# m907-vu-meter.net
KiCad netlist of a schematic drawn in EAGLE
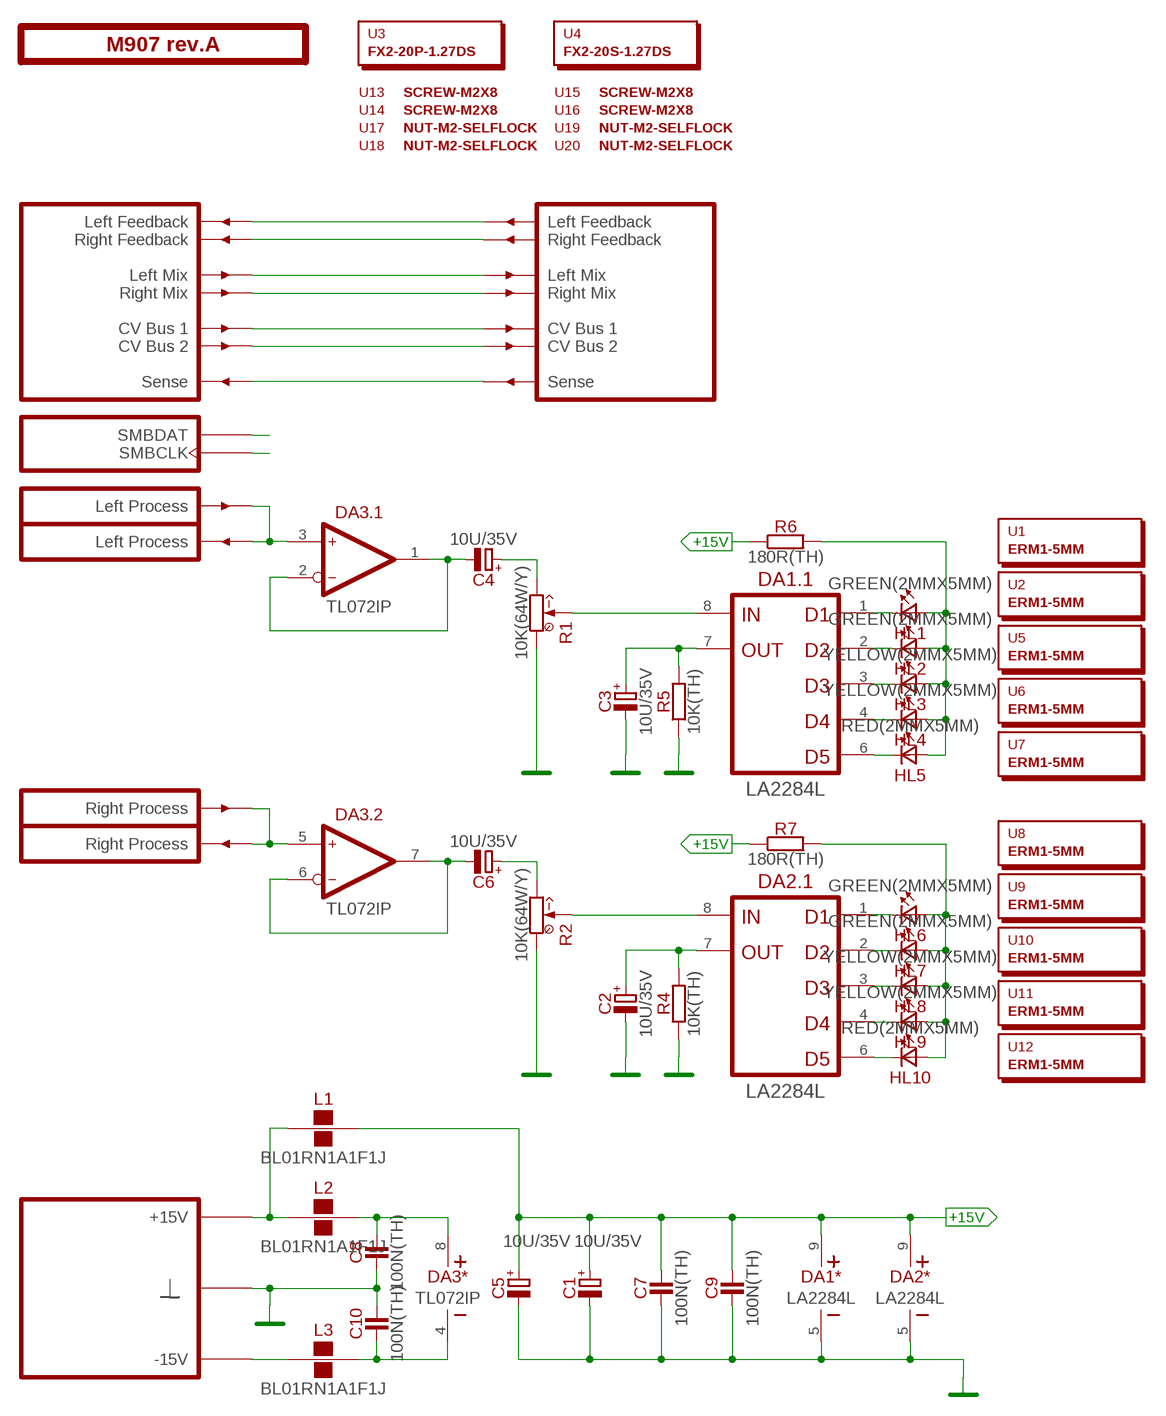
[diagram p0: schematic, sheet 1]

(export (version "E")
  (design (tool "Eeschema 10.0.6"))
  (components
    (comp (ref "C1")
      (value "10U/35V")
      (footprint "eagle-import:E2-5")
      (libsource (lib "eagle-import") (part "?10U/35V"))
    )
    (comp (ref "C2")
      (value "10U/35V")
      (footprint "eagle-import:E2-5")
      (libsource (lib "eagle-import") (part "?10U/35V"))
    )
    (comp (ref "C3")
      (value "10U/35V")
      (footprint "eagle-import:E2-5")
      (libsource (lib "eagle-import") (part "?10U/35V"))
    )
    (comp (ref "C4")
      (value "10U/35V")
      (footprint "eagle-import:E2-5")
      (libsource (lib "eagle-import") (part "?10U/35V"))
    )
    (comp (ref "C5")
      (value "10U/35V")
      (footprint "eagle-import:E2-5")
      (libsource (lib "eagle-import") (part "?10U/35V"))
    )
    (comp (ref "C6")
      (value "10U/35V")
      (footprint "eagle-import:E2-5")
      (libsource (lib "eagle-import") (part "?10U/35V"))
    )
    (comp (ref "C7")
      (value "100N(TH)")
      (footprint "eagle-import:C050-024X044")
      (libsource (lib "eagle-import") (part "?100N(TH)"))
    )
    (comp (ref "C8")
      (value "100N(TH)")
      (footprint "eagle-import:C050-024X044")
      (libsource (lib "eagle-import") (part "?100N(TH)"))
    )
    (comp (ref "C9")
      (value "100N(TH)")
      (footprint "eagle-import:C050-024X044")
      (libsource (lib "eagle-import") (part "?100N(TH)"))
    )
    (comp (ref "C10")
      (value "100N(TH)")
      (footprint "eagle-import:C050-024X044")
      (libsource (lib "eagle-import") (part "?100N(TH)"))
    )
    (comp (ref "DA1")
      (value "LA2284L")
      (footprint "eagle-import:SIL9")
      (libsource (lib "eagle-import") (part "LA2284L"))
    )
    (comp (ref "DA2")
      (value "LA2284L")
      (footprint "eagle-import:SIL9")
      (libsource (lib "eagle-import") (part "LA2284L"))
    )
    (comp (ref "DA3")
      (value "TL072IP")
      (footprint "eagle-import:DIP-8")
      (libsource (lib "eagle-import") (part "TL072IP"))
    )
    (comp (ref "HL1")
      (value "GREEN(2MMX5MM)")
      (footprint "eagle-import:LED2X5")
      (libsource (lib "eagle-import") (part "?(2MMX5MM)GREEN"))
    )
    (comp (ref "HL2")
      (value "GREEN(2MMX5MM)")
      (footprint "eagle-import:LED2X5")
      (libsource (lib "eagle-import") (part "?(2MMX5MM)GREEN"))
    )
    (comp (ref "HL3")
      (value "YELLOW(2MMX5MM)")
      (footprint "eagle-import:LED2X5")
      (libsource (lib "eagle-import") (part "?(2MMX5MM)YELLOW"))
    )
    (comp (ref "HL4")
      (value "YELLOW(2MMX5MM)")
      (footprint "eagle-import:LED2X5")
      (libsource (lib "eagle-import") (part "?(2MMX5MM)YELLOW"))
    )
    (comp (ref "HL5")
      (value "RED(2MMX5MM)")
      (footprint "eagle-import:LED2X5")
      (libsource (lib "eagle-import") (part "?(2MMX5MM)RED"))
    )
    (comp (ref "HL6")
      (value "GREEN(2MMX5MM)")
      (footprint "eagle-import:LED2X5")
      (libsource (lib "eagle-import") (part "?(2MMX5MM)GREEN"))
    )
    (comp (ref "HL7")
      (value "GREEN(2MMX5MM)")
      (footprint "eagle-import:LED2X5")
      (libsource (lib "eagle-import") (part "?(2MMX5MM)GREEN"))
    )
    (comp (ref "HL8")
      (value "YELLOW(2MMX5MM)")
      (footprint "eagle-import:LED2X5")
      (libsource (lib "eagle-import") (part "?(2MMX5MM)YELLOW"))
    )
    (comp (ref "HL9")
      (value "YELLOW(2MMX5MM)")
      (footprint "eagle-import:LED2X5")
      (libsource (lib "eagle-import") (part "?(2MMX5MM)YELLOW"))
    )
    (comp (ref "HL10")
      (value "RED(2MMX5MM)")
      (footprint "eagle-import:LED2X5")
      (libsource (lib "eagle-import") (part "?(2MMX5MM)RED"))
    )
    (comp (ref "L1")
      (value "BL01RN1A1F1J")
      (footprint "eagle-import:BL01RN1A")
      (libsource (lib "eagle-import") (part "BL01RN1A?1F1J"))
    )
    (comp (ref "L2")
      (value "BL01RN1A1F1J")
      (footprint "eagle-import:BL01RN1A")
      (libsource (lib "eagle-import") (part "BL01RN1A?1F1J"))
    )
    (comp (ref "L3")
      (value "BL01RN1A1F1J")
      (footprint "eagle-import:BL01RN1A")
      (libsource (lib "eagle-import") (part "BL01RN1A?1F1J"))
    )
    (comp (ref "PCB1")
      (value "M907 rev.A")
      (footprint "eagle-import:ST2-BOARD-26")
      (libsource (lib "eagle-import") (part "ST2-BOARD-?26"))
    )
    (comp (ref "R1")
      (value "10K(64W/Y)")
      (footprint "eagle-import:64W")
      (libsource (lib "eagle-import") (part "?(64W/Y)10K"))
    )
    (comp (ref "R2")
      (value "10K(64W/Y)")
      (footprint "eagle-import:64W")
      (libsource (lib "eagle-import") (part "?(64W/Y)10K"))
    )
    (comp (ref "R4")
      (value "10K(TH)")
      (footprint "eagle-import:R-0207_10")
      (libsource (lib "eagle-import") (part "?10K(TH)"))
    )
    (comp (ref "R5")
      (value "10K(TH)")
      (footprint "eagle-import:R-0207_10")
      (libsource (lib "eagle-import") (part "?10K(TH)"))
    )
    (comp (ref "R6")
      (value "180R(TH)")
      (footprint "eagle-import:R-0207_10")
      (libsource (lib "eagle-import") (part "?180R(TH)"))
    )
    (comp (ref "R7")
      (value "180R(TH)")
      (footprint "eagle-import:R-0207_10")
      (libsource (lib "eagle-import") (part "?180R(TH)"))
    )
    (comp (ref "U1")
      (value "ERM1-5MM")
      (footprint "eagle-import:EMPTY")
      (libsource (lib "eagle-import") (part "?ERM1-5MM"))
    )
    (comp (ref "U2")
      (value "ERM1-5MM")
      (footprint "eagle-import:EMPTY")
      (libsource (lib "eagle-import") (part "?ERM1-5MM"))
    )
    (comp (ref "U3")
      (value "FX2-20P-1.27DS")
      (footprint "eagle-import:EMPTY")
      (libsource (lib "eagle-import") (part "?FX2-20P-1.27DS"))
    )
    (comp (ref "U4")
      (value "FX2-20S-1.27DS")
      (footprint "eagle-import:EMPTY")
      (libsource (lib "eagle-import") (part "?FX2-20S-1.27DS"))
    )
    (comp (ref "U5")
      (value "ERM1-5MM")
      (footprint "eagle-import:EMPTY")
      (libsource (lib "eagle-import") (part "?ERM1-5MM"))
    )
    (comp (ref "U6")
      (value "ERM1-5MM")
      (footprint "eagle-import:EMPTY")
      (libsource (lib "eagle-import") (part "?ERM1-5MM"))
    )
    (comp (ref "U7")
      (value "ERM1-5MM")
      (footprint "eagle-import:EMPTY")
      (libsource (lib "eagle-import") (part "?ERM1-5MM"))
    )
    (comp (ref "U8")
      (value "ERM1-5MM")
      (footprint "eagle-import:EMPTY")
      (libsource (lib "eagle-import") (part "?ERM1-5MM"))
    )
    (comp (ref "U9")
      (value "ERM1-5MM")
      (footprint "eagle-import:EMPTY")
      (libsource (lib "eagle-import") (part "?ERM1-5MM"))
    )
    (comp (ref "U10")
      (value "ERM1-5MM")
      (footprint "eagle-import:EMPTY")
      (libsource (lib "eagle-import") (part "?ERM1-5MM"))
    )
    (comp (ref "U11")
      (value "ERM1-5MM")
      (footprint "eagle-import:EMPTY")
      (libsource (lib "eagle-import") (part "?ERM1-5MM"))
    )
    (comp (ref "U12")
      (value "ERM1-5MM")
      (footprint "eagle-import:EMPTY")
      (libsource (lib "eagle-import") (part "?ERM1-5MM"))
    )
    (comp (ref "U13")
      (value "SCREW-M2X8")
      (footprint "eagle-import:EMPTY")
      (libsource (lib "eagle-import") (part "?SCREW-M2X8"))
    )
    (comp (ref "U14")
      (value "SCREW-M2X8")
      (footprint "eagle-import:EMPTY")
      (libsource (lib "eagle-import") (part "?SCREW-M2X8"))
    )
    (comp (ref "U15")
      (value "SCREW-M2X8")
      (footprint "eagle-import:EMPTY")
      (libsource (lib "eagle-import") (part "?SCREW-M2X8"))
    )
    (comp (ref "U16")
      (value "SCREW-M2X8")
      (footprint "eagle-import:EMPTY")
      (libsource (lib "eagle-import") (part "?SCREW-M2X8"))
    )
    (comp (ref "U17")
      (value "NUT-M2-SELFLOCK")
      (footprint "eagle-import:EMPTY")
      (libsource (lib "eagle-import") (part "?NUT-M2-SELFLOCK"))
    )
    (comp (ref "U18")
      (value "NUT-M2-SELFLOCK")
      (footprint "eagle-import:EMPTY")
      (libsource (lib "eagle-import") (part "?NUT-M2-SELFLOCK"))
    )
    (comp (ref "U19")
      (value "NUT-M2-SELFLOCK")
      (footprint "eagle-import:EMPTY")
      (libsource (lib "eagle-import") (part "?NUT-M2-SELFLOCK"))
    )
    (comp (ref "U20")
      (value "NUT-M2-SELFLOCK")
      (footprint "eagle-import:EMPTY")
      (libsource (lib "eagle-import") (part "?NUT-M2-SELFLOCK"))
    )
  )
  (nets
    (net (code "1") (name "+15V") (class "Default")
      (node (ref "C1") (pin "+") (pinfunction "+_+") (pintype "passive"))
      (node (ref "C5") (pin "+") (pinfunction "+_+") (pintype "passive"))
      (node (ref "C7") (pin "2") (pinfunction "2_2") (pintype "passive"))
      (node (ref "C9") (pin "2") (pinfunction "2_2") (pintype "passive"))
      (node (ref "DA1") (pin "9") (pinfunction "V+_9") (pintype "power_in"))
      (node (ref "DA2") (pin "9") (pinfunction "V+_9") (pintype "power_in"))
      (node (ref "L1") (pin "2") (pinfunction "2_2") (pintype "passive"))
      (node (ref "R6") (pin "1") (pinfunction "1_1") (pintype "passive"))
      (node (ref "R7") (pin "1") (pinfunction "1_1") (pintype "passive"))
    )
    (net (code "2") (name "GND") (class "Default")
      (node (ref "C1") (pin "-") (pinfunction "-_-") (pintype "passive"))
      (node (ref "C10") (pin "2") (pinfunction "2_2") (pintype "passive"))
      (node (ref "C2") (pin "-") (pinfunction "-_-") (pintype "passive"))
      (node (ref "C3") (pin "-") (pinfunction "-_-") (pintype "passive"))
      (node (ref "C5") (pin "-") (pinfunction "-_-") (pintype "passive"))
      (node (ref "C7") (pin "1") (pinfunction "1_1") (pintype "passive"))
      (node (ref "C8") (pin "1") (pinfunction "1_1") (pintype "passive"))
      (node (ref "C9") (pin "1") (pinfunction "1_1") (pintype "passive"))
      (node (ref "DA1") (pin "5") (pinfunction "V-_5") (pintype "power_in"))
      (node (ref "DA2") (pin "5") (pinfunction "V-_5") (pintype "power_in"))
      (node (ref "PCB1") (pin "B4") (pinfunction "GND_B4") (pintype "bidirectional"))
      (node (ref "PCB1") (pin "B4'") (pinfunction "GND_B4'") (pintype "bidirectional"))
      (node (ref "PCB1") (pin "B5") (pinfunction "GND_B5") (pintype "bidirectional"))
      (node (ref "PCB1") (pin "B5'") (pinfunction "GND_B5'") (pintype "bidirectional"))
      (node (ref "PCB1") (pin "B6") (pinfunction "GND_B6") (pintype "bidirectional"))
      (node (ref "PCB1") (pin "B6'") (pinfunction "GND_B6'") (pintype "bidirectional"))
      (node (ref "PCB1") (pin "B7") (pinfunction "GND_B7") (pintype "bidirectional"))
      (node (ref "PCB1") (pin "B7'") (pinfunction "GND_B7'") (pintype "bidirectional"))
      (node (ref "PCB1") (pin "B8") (pinfunction "GND_B8") (pintype "bidirectional"))
      (node (ref "PCB1") (pin "B8'") (pinfunction "GND_B8'") (pintype "bidirectional"))
      (node (ref "R1") (pin "1") (pinfunction "CCW_1") (pintype "passive"))
      (node (ref "R2") (pin "1") (pinfunction "CCW_1") (pintype "passive"))
      (node (ref "R4") (pin "1") (pinfunction "1_1") (pintype "passive"))
      (node (ref "R5") (pin "1") (pinfunction "1_1") (pintype "passive"))
    )
    (net (code "3") (name "Net-(DA1B-D1)") (class "Default")
      (node (ref "DA1") (pin "1") (pinfunction "D1_1") (pintype "input"))
      (node (ref "HL1") (pin "K") (pinfunction "C_K") (pintype "passive"))
    )
    (net (code "4") (name "Net-(DA1B-D2)") (class "Default")
      (node (ref "DA1") (pin "2") (pinfunction "D2_2") (pintype "input"))
      (node (ref "HL2") (pin "K") (pinfunction "C_K") (pintype "passive"))
    )
    (net (code "5") (name "Net-(DA1B-D3)") (class "Default")
      (node (ref "DA1") (pin "3") (pinfunction "D3_3") (pintype "input"))
      (node (ref "HL3") (pin "K") (pinfunction "C_K") (pintype "passive"))
    )
    (net (code "6") (name "Net-(DA1B-D4)") (class "Default")
      (node (ref "DA1") (pin "4") (pinfunction "D4_4") (pintype "input"))
      (node (ref "HL4") (pin "K") (pinfunction "C_K") (pintype "passive"))
    )
    (net (code "7") (name "Net-(DA1B-D5)") (class "Default")
      (node (ref "DA1") (pin "6") (pinfunction "D5_6") (pintype "input"))
      (node (ref "HL5") (pin "K") (pinfunction "C_K") (pintype "passive"))
    )
    (net (code "8") (name "Net-(DA1B-IN)") (class "Default")
      (node (ref "DA1") (pin "8") (pinfunction "IN_8") (pintype "input"))
      (node (ref "R1") (pin "S") (pinfunction "W_S") (pintype "passive"))
      (node (ref "R1") (pin "S@1") (pinfunction "W_S@1") (pintype "passive"))
    )
    (net (code "9") (name "Net-(DA1B-OUT)") (class "Default")
      (node (ref "C3") (pin "+") (pinfunction "+_+") (pintype "passive"))
      (node (ref "DA1") (pin "7") (pinfunction "OUT_7") (pintype "input"))
      (node (ref "R5") (pin "2") (pinfunction "2_2") (pintype "passive"))
    )
    (net (code "10") (name "Net-(DA2B-D1)") (class "Default")
      (node (ref "DA2") (pin "1") (pinfunction "D1_1") (pintype "input"))
      (node (ref "HL6") (pin "K") (pinfunction "C_K") (pintype "passive"))
    )
    (net (code "11") (name "Net-(DA2B-D2)") (class "Default")
      (node (ref "DA2") (pin "2") (pinfunction "D2_2") (pintype "input"))
      (node (ref "HL7") (pin "K") (pinfunction "C_K") (pintype "passive"))
    )
    (net (code "12") (name "Net-(DA2B-D3)") (class "Default")
      (node (ref "DA2") (pin "3") (pinfunction "D3_3") (pintype "input"))
      (node (ref "HL8") (pin "K") (pinfunction "C_K") (pintype "passive"))
    )
    (net (code "13") (name "Net-(DA2B-D4)") (class "Default")
      (node (ref "DA2") (pin "4") (pinfunction "D4_4") (pintype "input"))
      (node (ref "HL9") (pin "K") (pinfunction "C_K") (pintype "passive"))
    )
    (net (code "14") (name "Net-(DA2B-D5)") (class "Default")
      (node (ref "DA2") (pin "6") (pinfunction "D5_6") (pintype "input"))
      (node (ref "HL10") (pin "K") (pinfunction "C_K") (pintype "passive"))
    )
    (net (code "15") (name "Net-(DA2B-IN)") (class "Default")
      (node (ref "DA2") (pin "8") (pinfunction "IN_8") (pintype "input"))
      (node (ref "R2") (pin "S") (pinfunction "W_S") (pintype "passive"))
      (node (ref "R2") (pin "S@1") (pinfunction "W_S@1") (pintype "passive"))
    )
    (net (code "16") (name "Net-(DA2B-OUT)") (class "Default")
      (node (ref "C2") (pin "+") (pinfunction "+_+") (pintype "passive"))
      (node (ref "DA2") (pin "7") (pinfunction "OUT_7") (pintype "input"))
      (node (ref "R4") (pin "2") (pinfunction "2_2") (pintype "passive"))
    )
    (net (code "17") (name "Net-(DA3A-V+)") (class "Default")
      (node (ref "C8") (pin "2") (pinfunction "2_2") (pintype "passive"))
      (node (ref "DA3") (pin "8") (pinfunction "V+_8") (pintype "power_in"))
      (node (ref "L2") (pin "2") (pinfunction "2_2") (pintype "passive"))
    )
    (net (code "18") (name "Net-(DA3A-V-)") (class "Default")
      (node (ref "C10") (pin "1") (pinfunction "1_1") (pintype "passive"))
      (node (ref "DA3") (pin "4") (pinfunction "V-_4") (pintype "power_in"))
      (node (ref "L3") (pin "2") (pinfunction "2_2") (pintype "passive"))
    )
    (net (code "19") (name "Net-(DA3B-IN+)") (class "Default")
      (node (ref "DA3") (pin "3") (pinfunction "IN+_3") (pintype "input"))
      (node (ref "PCB1") (pin "BINL") (pinfunction "INL_BINL") (pintype "bidirectional"))
      (node (ref "PCB1") (pin "BOUTL'") (pinfunction "OUTL_BOUTL'") (pintype "bidirectional"))
    )
    (net (code "20") (name "Net-(DA3B-IN-)") (class "Default")
      (node (ref "C4") (pin "-") (pinfunction "-_-") (pintype "passive"))
      (node (ref "DA3") (pin "1") (pinfunction "OUT_1") (pintype "output"))
      (node (ref "DA3") (pin "2") (pinfunction "IN-_2") (pintype "input"))
    )
    (net (code "21") (name "Net-(DA3C-IN+)") (class "Default")
      (node (ref "DA3") (pin "5") (pinfunction "IN+_5") (pintype "input"))
      (node (ref "PCB1") (pin "BINR") (pinfunction "INR_BINR") (pintype "bidirectional"))
      (node (ref "PCB1") (pin "BOUTR'") (pinfunction "OUTR_BOUTR'") (pintype "bidirectional"))
    )
    (net (code "22") (name "Net-(DA3C-IN-)") (class "Default")
      (node (ref "C6") (pin "-") (pinfunction "-_-") (pintype "passive"))
      (node (ref "DA3") (pin "6") (pinfunction "IN-_6") (pintype "input"))
      (node (ref "DA3") (pin "7") (pinfunction "OUT_7") (pintype "output"))
    )
    (net (code "23") (name "Net-(HL1-PadA)") (class "Default")
      (node (ref "HL1") (pin "A") (pinfunction "A_A") (pintype "passive"))
      (node (ref "HL2") (pin "A") (pinfunction "A_A") (pintype "passive"))
      (node (ref "HL3") (pin "A") (pinfunction "A_A") (pintype "passive"))
      (node (ref "HL4") (pin "A") (pinfunction "A_A") (pintype "passive"))
      (node (ref "HL5") (pin "A") (pinfunction "A_A") (pintype "passive"))
      (node (ref "R6") (pin "2") (pinfunction "2_2") (pintype "passive"))
    )
    (net (code "24") (name "Net-(HL10-PadA)") (class "Default")
      (node (ref "HL10") (pin "A") (pinfunction "A_A") (pintype "passive"))
      (node (ref "HL6") (pin "A") (pinfunction "A_A") (pintype "passive"))
      (node (ref "HL7") (pin "A") (pinfunction "A_A") (pintype "passive"))
      (node (ref "HL8") (pin "A") (pinfunction "A_A") (pintype "passive"))
      (node (ref "HL9") (pin "A") (pinfunction "A_A") (pintype "passive"))
      (node (ref "R7") (pin "2") (pinfunction "2_2") (pintype "passive"))
    )
    (net (code "25") (name "Net-(L1-Pad1)") (class "Default")
      (node (ref "L1") (pin "1") (pinfunction "1_1") (pintype "passive"))
      (node (ref "L2") (pin "1") (pinfunction "1_1") (pintype "passive"))
      (node (ref "PCB1") (pin "A+15") (pinfunction "P+15V_A+15") (pintype "bidirectional"))
      (node (ref "PCB1") (pin "A+15'") (pinfunction "P+15V_A+15'") (pintype "bidirectional"))
      (node (ref "PCB1") (pin "B+15") (pinfunction "P+15V_B+15") (pintype "bidirectional"))
      (node (ref "PCB1") (pin "B+15'") (pinfunction "P+15V_B+15'") (pintype "bidirectional"))
    )
    (net (code "26") (name "Net-(L3-Pad1)") (class "Default")
      (node (ref "L3") (pin "1") (pinfunction "1_1") (pintype "passive"))
      (node (ref "PCB1") (pin "A-15") (pinfunction "P-15V_A-15") (pintype "bidirectional"))
      (node (ref "PCB1") (pin "A-15'") (pinfunction "P-15V_A-15'") (pintype "bidirectional"))
      (node (ref "PCB1") (pin "B-15") (pinfunction "P-15V_B-15") (pintype "bidirectional"))
      (node (ref "PCB1") (pin "B-15'") (pinfunction "P-15V_B-15'") (pintype "bidirectional"))
    )
    (net (code "27") (name "Net-(PCB1F-CV1)") (class "Default")
      (node (ref "PCB1") (pin "ACV1") (pinfunction "CV1_ACV1") (pintype "bidirectional"))
      (node (ref "PCB1") (pin "ACV1'") (pinfunction "CV1'_ACV1'") (pintype "bidirectional"))
    )
    (net (code "28") (name "Net-(PCB1F-CV2)") (class "Default")
      (node (ref "PCB1") (pin "ACV2") (pinfunction "CV2_ACV2") (pintype "bidirectional"))
      (node (ref "PCB1") (pin "ACV2'") (pinfunction "CV2'_ACV2'") (pintype "bidirectional"))
    )
    (net (code "29") (name "Net-(PCB1F-LFBK)") (class "Default")
      (node (ref "PCB1") (pin "ALFBK") (pinfunction "LFBK_ALFBK") (pintype "bidirectional"))
      (node (ref "PCB1") (pin "ALFBK'") (pinfunction "LFBK'_ALFBK'") (pintype "bidirectional"))
    )
    (net (code "30") (name "Net-(PCB1F-LMIX)") (class "Default")
      (node (ref "PCB1") (pin "ALMIX") (pinfunction "LMIX_ALMIX") (pintype "bidirectional"))
      (node (ref "PCB1") (pin "ALMIX'") (pinfunction "LMIX'_ALMIX'") (pintype "bidirectional"))
    )
    (net (code "31") (name "Net-(PCB1F-RFBK)") (class "Default")
      (node (ref "PCB1") (pin "ARFBK") (pinfunction "RFBK_ARFBK") (pintype "bidirectional"))
      (node (ref "PCB1") (pin "ARFBK'") (pinfunction "RFBK'_ARFBK'") (pintype "bidirectional"))
    )
    (net (code "32") (name "Net-(PCB1F-RMIX)") (class "Default")
      (node (ref "PCB1") (pin "ARMIX") (pinfunction "RMIX_ARMIX") (pintype "bidirectional"))
      (node (ref "PCB1") (pin "ARMIX'") (pinfunction "RMIX'_ARMIX'") (pintype "bidirectional"))
    )
    (net (code "33") (name "Net-(PCB1F-SENSE)") (class "Default")
      (node (ref "PCB1") (pin "BSENSE") (pinfunction "SENSE_BSENSE") (pintype "bidirectional"))
      (node (ref "PCB1") (pin "BSENSE'") (pinfunction "SENSE'_BSENSE'") (pintype "bidirectional"))
    )
    (net (code "34") (name "Net-(PCB1H-SMBCLK-PadASMBCLK')") (class "Default")
      (node (ref "PCB1") (pin "ASMBCLK") (pinfunction "SMBCLK_ASMBCLK") (pintype "bidirectional"))
      (node (ref "PCB1") (pin "ASMBCLK'") (pinfunction "SMBCLK_ASMBCLK'") (pintype "bidirectional"))
    )
    (net (code "35") (name "Net-(PCB1H-SMBDAT-PadASMBDAT')") (class "Default")
      (node (ref "PCB1") (pin "ASMBDAT") (pinfunction "SMBDAT_ASMBDAT") (pintype "bidirectional"))
      (node (ref "PCB1") (pin "ASMBDAT'") (pinfunction "SMBDAT_ASMBDAT'") (pintype "bidirectional"))
    )
    (net (code "36") (name "Net-(R1-CW)") (class "Default")
      (node (ref "C4") (pin "+") (pinfunction "+_+") (pintype "passive"))
      (node (ref "R1") (pin "3") (pinfunction "CW_3") (pintype "passive"))
    )
    (net (code "37") (name "Net-(R2-CW)") (class "Default")
      (node (ref "C6") (pin "+") (pinfunction "+_+") (pintype "passive"))
      (node (ref "R2") (pin "3") (pinfunction "CW_3") (pintype "passive"))
    )
  )
)
